# v1.net
KiCad netlist of a schematic drawn in EAGLE
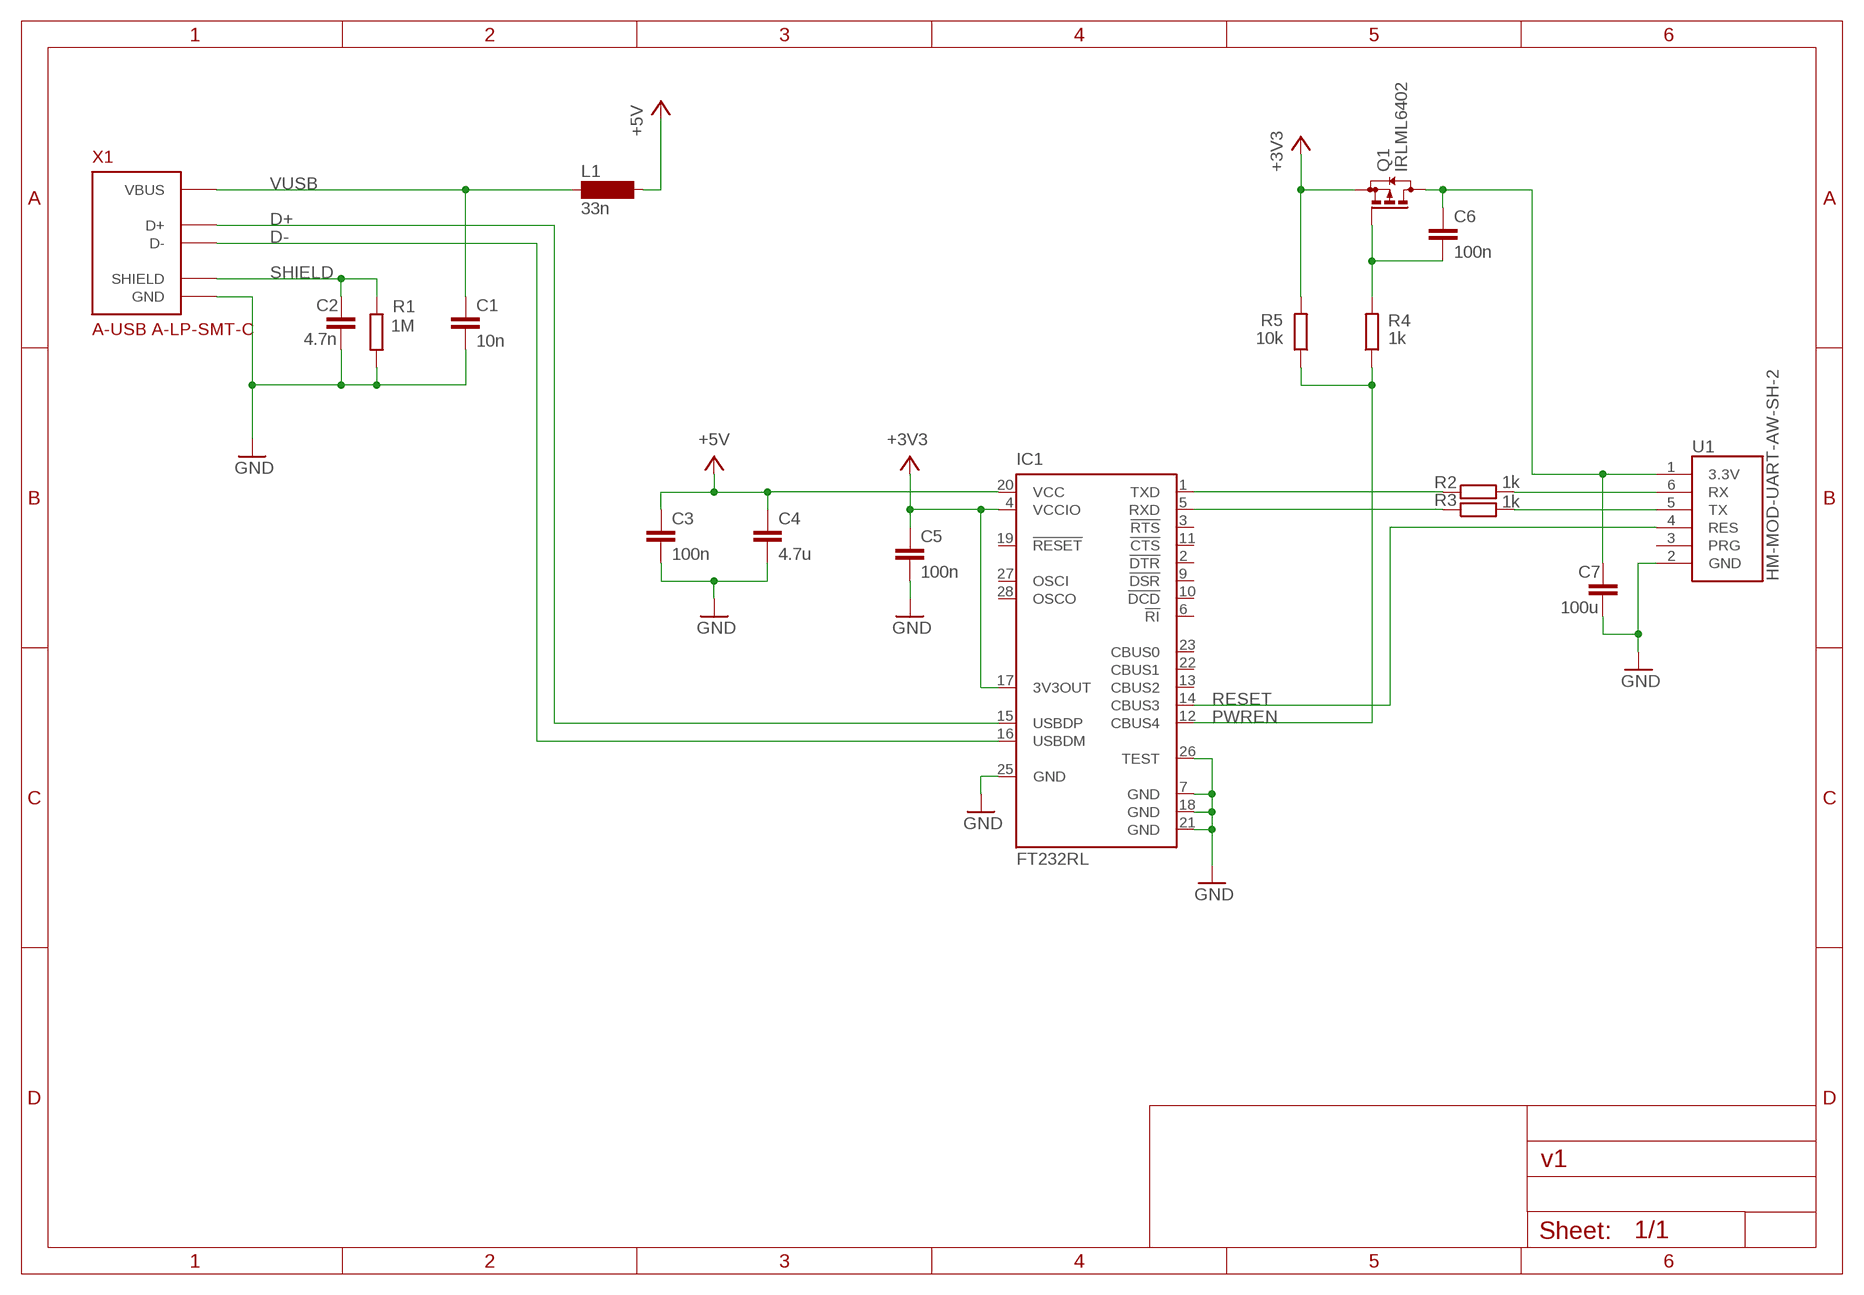
[diagram p0: schematic, sheet 1]

(export (version "E")
  (design (tool "Eeschema 10.0.6"))
  (components
    (comp (ref "C1")
      (value "10n")
      (footprint "eagle-import:C1206")
      (libsource (lib "eagle-import") (part "C-EUC1206"))
    )
    (comp (ref "C2")
      (value "4.7n")
      (footprint "eagle-import:C1206")
      (libsource (lib "eagle-import") (part "C-EUC1206"))
    )
    (comp (ref "C3")
      (value "100n")
      (footprint "eagle-import:C1206")
      (libsource (lib "eagle-import") (part "C-EUC1206"))
    )
    (comp (ref "C4")
      (value "4.7u")
      (footprint "eagle-import:C1206")
      (libsource (lib "eagle-import") (part "C-EUC1206"))
    )
    (comp (ref "C5")
      (value "100n")
      (footprint "eagle-import:C1206")
      (libsource (lib "eagle-import") (part "C-EUC1206"))
    )
    (comp (ref "C6")
      (value "100n")
      (footprint "eagle-import:C1206")
      (libsource (lib "eagle-import") (part "C-EUC1206"))
    )
    (comp (ref "C7")
      (value "100u")
      (footprint "eagle-import:C1206")
      (libsource (lib "eagle-import") (part "C-EUC1206"))
    )
    (comp (ref "IC1")
      (value "FT232RL")
      (footprint "eagle-import:SSOP28")
      (libsource (lib "eagle-import") (part "FT232RL"))
    )
    (comp (ref "L1")
      (value "33n")
      (footprint "eagle-import:SM-1206")
      (libsource (lib "eagle-import") (part "SM-1206"))
    )
    (comp (ref "Q1")
      (value "IRLML6402")
      (footprint "eagle-import:SOT23")
      (libsource (lib "eagle-import") (part "BSS84"))
    )
    (comp (ref "R1")
      (value "1M")
      (footprint "eagle-import:R1206")
      (libsource (lib "eagle-import") (part "R-EU_R1206"))
    )
    (comp (ref "R2")
      (value "1k")
      (footprint "eagle-import:R1206")
      (libsource (lib "eagle-import") (part "R-EU_R1206"))
    )
    (comp (ref "R3")
      (value "1k")
      (footprint "eagle-import:R1206")
      (libsource (lib "eagle-import") (part "R-EU_R1206"))
    )
    (comp (ref "R4")
      (value "1k")
      (footprint "eagle-import:R1206")
      (libsource (lib "eagle-import") (part "R-EU_R1206"))
    )
    (comp (ref "R5")
      (value "10k")
      (footprint "eagle-import:R1206")
      (libsource (lib "eagle-import") (part "R-EU_R1206"))
    )
    (comp (ref "U1")
      (value "HM-MOD-UART-AW-SH-2")
      (footprint "eagle-import:HM-MOD-UART-AW-SH-2_SMD")
      (libsource (lib "eagle-import") (part "HM-MOD-UART-AW-SH-2_SMD"))
    )
    (comp (ref "X1")
      (value "A-USB A-LP-SMT-C")
      (footprint "eagle-import:A-USB_A-LP-SMT-C")
      (libsource (lib "eagle-import") (part "USB-1.0/1.1/2.0-STANDARD-A/B_A-LP-SMT-C"))
    )
  )
  (nets
    (net (code "1") (name "+3V3") (class "Default")
      (node (ref "C5") (pin "1") (pinfunction "1_1") (pintype "passive"))
      (node (ref "IC1") (pin "17") (pinfunction "3V3OUT_17") (pintype "output"))
      (node (ref "IC1") (pin "4") (pinfunction "VCCIO_4") (pintype "power_in"))
      (node (ref "Q1") (pin "2") (pinfunction "S_2") (pintype "passive"))
      (node (ref "R5") (pin "2") (pinfunction "2_2") (pintype "passive"))
    )
    (net (code "2") (name "+5V") (class "Default")
      (node (ref "C3") (pin "1") (pinfunction "1_1") (pintype "passive"))
      (node (ref "C4") (pin "1") (pinfunction "1_1") (pintype "passive"))
      (node (ref "IC1") (pin "20") (pinfunction "VCC_20") (pintype "power_in"))
      (node (ref "L1") (pin "2") (pinfunction "2_2") (pintype "passive"))
    )
    (net (code "3") (name "/D+") (class "Default")
      (node (ref "IC1") (pin "15") (pinfunction "USBDP_15") (pintype "bidirectional"))
      (node (ref "X1") (pin "3") (pinfunction "D+_3") (pintype "bidirectional"))
    )
    (net (code "4") (name "/D-") (class "Default")
      (node (ref "IC1") (pin "16") (pinfunction "USBDM_16") (pintype "bidirectional"))
      (node (ref "X1") (pin "2") (pinfunction "D-_2") (pintype "bidirectional"))
    )
    (net (code "5") (name "/PWREN") (class "Default")
      (node (ref "IC1") (pin "12") (pinfunction "CBUS4_12") (pintype "bidirectional"))
      (node (ref "R4") (pin "1") (pinfunction "1_1") (pintype "passive"))
      (node (ref "R5") (pin "1") (pinfunction "1_1") (pintype "passive"))
    )
    (net (code "6") (name "/RESET") (class "Default")
      (node (ref "IC1") (pin "14") (pinfunction "CBUS3_14") (pintype "bidirectional"))
      (node (ref "U1") (pin "4") (pinfunction "RES_4") (pintype "input"))
    )
    (net (code "7") (name "/SHIELD") (class "Default")
      (node (ref "C2") (pin "1") (pinfunction "1_1") (pintype "passive"))
      (node (ref "R1") (pin "1") (pinfunction "1_1") (pintype "passive"))
      (node (ref "X1") (pin "S1") (pinfunction "SHIELD_S1") (pintype "bidirectional"))
      (node (ref "X1") (pin "S2") (pinfunction "SHIELD_S2") (pintype "bidirectional"))
    )
    (net (code "8") (name "/VUSB") (class "Default")
      (node (ref "C1") (pin "1") (pinfunction "1_1") (pintype "passive"))
      (node (ref "L1") (pin "1") (pinfunction "1_1") (pintype "passive"))
      (node (ref "X1") (pin "1") (pinfunction "VBUS_1") (pintype "bidirectional"))
    )
    (net (code "9") (name "GND") (class "Default")
      (node (ref "C1") (pin "2") (pinfunction "2_2") (pintype "passive"))
      (node (ref "C2") (pin "2") (pinfunction "2_2") (pintype "passive"))
      (node (ref "C3") (pin "2") (pinfunction "2_2") (pintype "passive"))
      (node (ref "C4") (pin "2") (pinfunction "2_2") (pintype "passive"))
      (node (ref "C5") (pin "2") (pinfunction "2_2") (pintype "passive"))
      (node (ref "C7") (pin "2") (pinfunction "2_2") (pintype "passive"))
      (node (ref "IC1") (pin "18") (pinfunction "GND_18") (pintype "power_in"))
      (node (ref "IC1") (pin "21") (pinfunction "GND_21") (pintype "power_in"))
      (node (ref "IC1") (pin "25") (pinfunction "GND_25") (pintype "power_in"))
      (node (ref "IC1") (pin "26") (pinfunction "TEST_26") (pintype "input"))
      (node (ref "IC1") (pin "7") (pinfunction "GND_7") (pintype "power_in"))
      (node (ref "R1") (pin "2") (pinfunction "2_2") (pintype "passive"))
      (node (ref "U1") (pin "2") (pinfunction "GND_2") (pintype "power_in"))
      (node (ref "X1") (pin "4") (pinfunction "GND_4") (pintype "bidirectional"))
    )
    (net (code "10") (name "Net-(IC1-RXD)") (class "Default")
      (node (ref "IC1") (pin "5") (pinfunction "RXD_5") (pintype "input"))
      (node (ref "R3") (pin "1") (pinfunction "1_1") (pintype "passive"))
    )
    (net (code "11") (name "Net-(IC1-TXD)") (class "Default")
      (node (ref "IC1") (pin "1") (pinfunction "TXD_1") (pintype "output"))
      (node (ref "R2") (pin "1") (pinfunction "1_1") (pintype "passive"))
    )
    (net (code "12") (name "Net-(Q1-D)") (class "Default")
      (node (ref "C6") (pin "1") (pinfunction "1_1") (pintype "passive"))
      (node (ref "C7") (pin "1") (pinfunction "1_1") (pintype "passive"))
      (node (ref "Q1") (pin "3") (pinfunction "D_3") (pintype "passive"))
      (node (ref "U1") (pin "1") (pinfunction "3.3V_1") (pintype "power_in"))
    )
    (net (code "13") (name "Net-(Q1-G)") (class "Default")
      (node (ref "C6") (pin "2") (pinfunction "2_2") (pintype "passive"))
      (node (ref "Q1") (pin "1") (pinfunction "G_1") (pintype "passive"))
      (node (ref "R4") (pin "2") (pinfunction "2_2") (pintype "passive"))
    )
    (net (code "14") (name "Net-(U1-RX)") (class "Default")
      (node (ref "R2") (pin "2") (pinfunction "2_2") (pintype "passive"))
      (node (ref "U1") (pin "6") (pinfunction "RX_6") (pintype "input"))
    )
    (net (code "15") (name "Net-(U1-TX)") (class "Default")
      (node (ref "R3") (pin "2") (pinfunction "2_2") (pintype "passive"))
      (node (ref "U1") (pin "5") (pinfunction "TX_5") (pintype "output"))
    )
    (net (code "16") (name "unconnected-(IC1-CBUS0-Pad23)") (class "Default")
      (node (ref "IC1") (pin "23") (pinfunction "CBUS0_23") (pintype "bidirectional"))
    )
    (net (code "17") (name "unconnected-(IC1-CBUS1-Pad22)") (class "Default")
      (node (ref "IC1") (pin "22") (pinfunction "CBUS1_22") (pintype "bidirectional"))
    )
    (net (code "18") (name "unconnected-(IC1-CBUS2-Pad13)") (class "Default")
      (node (ref "IC1") (pin "13") (pinfunction "CBUS2_13") (pintype "bidirectional"))
    )
    (net (code "19") (name "unconnected-(IC1-OSCI-Pad27)") (class "Default")
      (node (ref "IC1") (pin "27") (pinfunction "OSCI_27") (pintype "input"))
    )
    (net (code "20") (name "unconnected-(IC1-OSCO-Pad28)") (class "Default")
      (node (ref "IC1") (pin "28") (pinfunction "OSCO_28") (pintype "output"))
    )
    (net (code "21") (name "unconnected-(IC1-~{CTS}-Pad11)") (class "Default")
      (node (ref "IC1") (pin "11") (pinfunction "~{CTS}_11") (pintype "input"))
    )
    (net (code "22") (name "unconnected-(IC1-~{DCD}-Pad10)") (class "Default")
      (node (ref "IC1") (pin "10") (pinfunction "~{DCD}_10") (pintype "input"))
    )
    (net (code "23") (name "unconnected-(IC1-~{DSR}-Pad9)") (class "Default")
      (node (ref "IC1") (pin "9") (pinfunction "~{DSR}_9") (pintype "input"))
    )
    (net (code "24") (name "unconnected-(IC1-~{DTR}-Pad2)") (class "Default")
      (node (ref "IC1") (pin "2") (pinfunction "~{DTR}_2") (pintype "output"))
    )
    (net (code "25") (name "unconnected-(IC1-~{RESET}-Pad19)") (class "Default")
      (node (ref "IC1") (pin "19") (pinfunction "~{RESET}_19") (pintype "input"))
    )
    (net (code "26") (name "unconnected-(IC1-~{RI}-Pad6)") (class "Default")
      (node (ref "IC1") (pin "6") (pinfunction "~{RI}_6") (pintype "input"))
    )
    (net (code "27") (name "unconnected-(IC1-~{RTS}-Pad3)") (class "Default")
      (node (ref "IC1") (pin "3") (pinfunction "~{RTS}_3") (pintype "output"))
    )
    (net (code "28") (name "unconnected-(U1-PRG-Pad3)") (class "Default")
      (node (ref "U1") (pin "3") (pinfunction "PRG_3") (pintype "input"))
    )
  )
)
